# 05_UART.net
KiCad netlist of a schematic drawn in Altium Designer
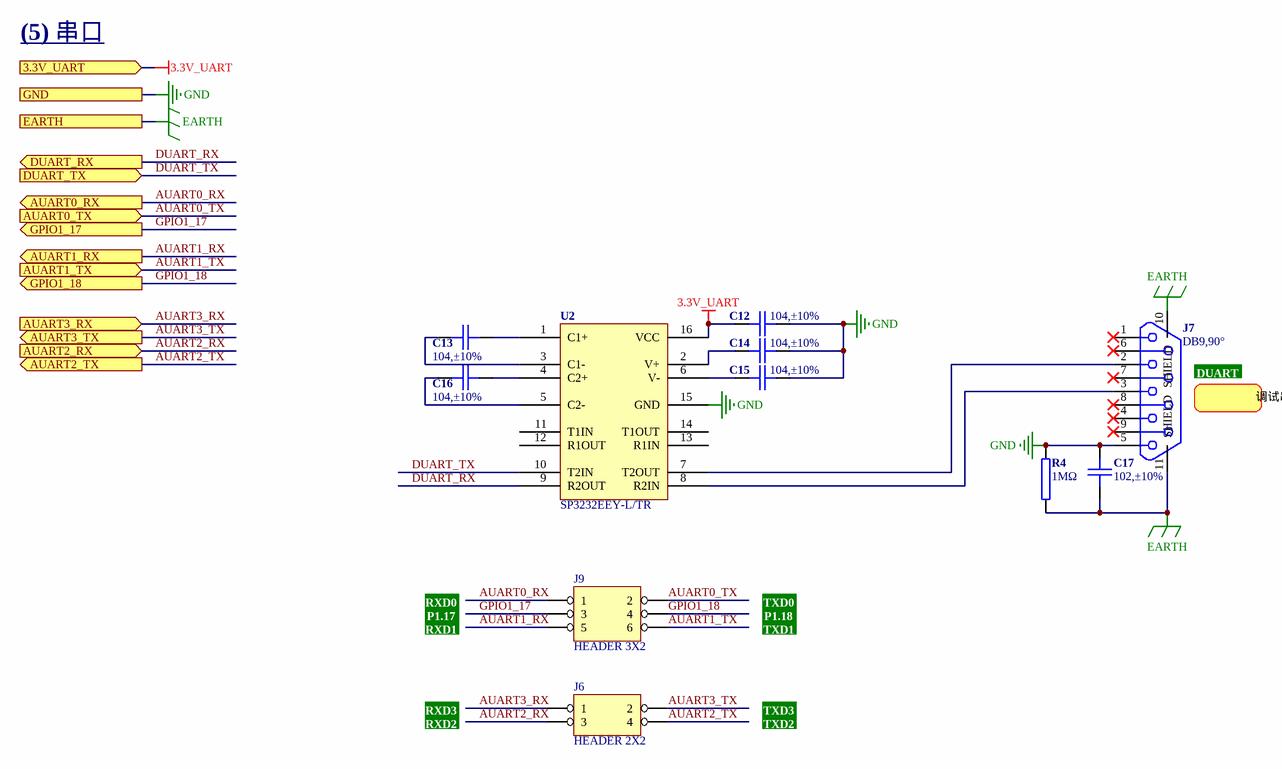
[diagram p0: 05. UART.SchDoc]

(export (version "E")
  (design (tool "Eeschema 10.0.6"))
  (components
    (comp (ref "C12")
      (value "104,±10%")
      (footprint "0603C")
      (description "104,±10%,50V,X7R,0603,*,RoHS")
      (libsource (lib "ErpMaterialData") (part "CAP1"))
    )
    (comp (ref "C13")
      (value "104,±10%")
      (footprint "0603C")
      (description "104,±10%,50V,X7R,0603,*,RoHS")
      (libsource (lib "ErpMaterialData") (part "CAP1"))
    )
    (comp (ref "C14")
      (value "104,±10%")
      (footprint "0603C")
      (description "104,±10%,50V,X7R,0603,*,RoHS")
      (libsource (lib "ErpMaterialData") (part "CAP1"))
    )
    (comp (ref "C15")
      (value "104,±10%")
      (footprint "0603C")
      (description "104,±10%,50V,X7R,0603,*,RoHS")
      (libsource (lib "ErpMaterialData") (part "CAP1"))
    )
    (comp (ref "C16")
      (value "104,±10%")
      (footprint "0603C")
      (description "104,±10%,50V,X7R,0603,*,RoHS")
      (libsource (lib "ErpMaterialData") (part "CAP1"))
    )
    (comp (ref "C17")
      (value "102,±10%")
      (footprint "1206C")
      (description "102,±10%,2KV,X7R,1206,*,RoHS")
      (libsource (lib "ErpMaterialData") (part "CAP1"))
    )
    (comp (ref "J6") (value "HEADER 2X2") (footprint "IDC-4") (libsource (lib "无需物料号元件") (part "HEADER 2X2")))
    (comp (ref "J7")
      (value "DB9,90°")
      (footprint "DB-9RA/F")
      (description "DB9,90°,孔,铆合,带螺丝")
      (fields (field (name "Comment") "DB9"))
      (libsource (lib "ErpMaterialData") (part "DB9"))
    )
    (comp (ref "J9") (value "HEADER 3X2") (footprint "IDC-6") (libsource (lib "无需物料号元件") (part "HEADER 3X2")))
    (comp (ref "R4")
      (value "1MΩ")
      (footprint "1206R")
      (description "1MΩ,1206,RoHS")
      (libsource (lib "ErpMaterialData") (part "RES2"))
    )
    (comp (ref "U2")
      (value "SP3232EEY-L/TR")
      (footprint "SOP65P640X120-16N")
      (description "SP3232EEY-L/TR,TSSOP-16,EXAR,RoHS")
      (fields (field (name "Comment") "SP3232E"))
      (libsource (lib "ErpMaterialData") (part "SP3232E"))
    )
  )
  (nets
    (net (code "1") (name "/AUART0_RX") (class "Default")
      (node (ref "J9") (pin "1") (pinfunction "1_1") (pintype "passive"))
    )
    (net (code "2") (name "/AUART0_TX") (class "Default")
      (node (ref "J9") (pin "2") (pinfunction "2_2") (pintype "passive"))
    )
    (net (code "3") (name "/AUART1_RX") (class "Default")
      (node (ref "J9") (pin "5") (pinfunction "5_5") (pintype "passive"))
    )
    (net (code "4") (name "/AUART1_TX") (class "Default")
      (node (ref "J9") (pin "6") (pinfunction "6_6") (pintype "passive"))
    )
    (net (code "5") (name "/AUART2_RX") (class "Default")
      (node (ref "J6") (pin "3") (pinfunction "3_3") (pintype "passive"))
    )
    (net (code "6") (name "/AUART2_TX") (class "Default")
      (node (ref "J6") (pin "4") (pinfunction "4_4") (pintype "passive"))
    )
    (net (code "7") (name "/AUART3_RX") (class "Default")
      (node (ref "J6") (pin "1") (pinfunction "1_1") (pintype "passive"))
    )
    (net (code "8") (name "/AUART3_TX") (class "Default")
      (node (ref "J6") (pin "2") (pinfunction "2_2") (pintype "passive"))
    )
    (net (code "9") (name "/DUART_RX") (class "Default")
      (node (ref "U2") (pin "9") (pinfunction "R2OUT_9") (pintype "passive"))
    )
    (net (code "10") (name "/DUART_TX") (class "Default")
      (node (ref "U2") (pin "10") (pinfunction "T2IN_10") (pintype "passive"))
    )
    (net (code "11") (name "/GPIO1_17") (class "Default")
      (node (ref "J9") (pin "3") (pinfunction "3_3") (pintype "passive"))
    )
    (net (code "12") (name "/GPIO1_18") (class "Default")
      (node (ref "J9") (pin "4") (pinfunction "4_4") (pintype "passive"))
    )
    (net (code "13") (name "3.3V_UART") (class "Default")
      (node (ref "C12") (pin "1") (pinfunction "1_1") (pintype "passive"))
      (node (ref "U2") (pin "16") (pinfunction "VCC_16") (pintype "passive"))
    )
    (net (code "14") (name "EARTH") (class "Default")
      (node (ref "C17") (pin "2") (pinfunction "2_2") (pintype "passive"))
      (node (ref "J7") (pin "10") (pinfunction "SHIELD_10") (pintype "passive"))
      (node (ref "J7") (pin "11") (pinfunction "SHIELD_11") (pintype "passive"))
      (node (ref "R4") (pin "1") (pinfunction "1_1") (pintype "passive"))
    )
    (net (code "15") (name "GND") (class "Default")
      (node (ref "C12") (pin "2") (pinfunction "2_2") (pintype "passive"))
      (node (ref "C14") (pin "2") (pinfunction "2_2") (pintype "passive"))
      (node (ref "C15") (pin "2") (pinfunction "2_2") (pintype "passive"))
      (node (ref "C17") (pin "1") (pinfunction "1_1") (pintype "passive"))
      (node (ref "J7") (pin "5") (pinfunction "5_5") (pintype "passive"))
      (node (ref "R4") (pin "2") (pinfunction "2_2") (pintype "passive"))
      (node (ref "U2") (pin "15") (pinfunction "GND_15") (pintype "passive"))
    )
    (net (code "16") (name "Net-(U2-C1+)") (class "Default")
      (node (ref "C13") (pin "2") (pinfunction "2_2") (pintype "passive"))
      (node (ref "U2") (pin "1") (pinfunction "C1+_1") (pintype "passive"))
    )
    (net (code "17") (name "Net-(U2-C1-)") (class "Default")
      (node (ref "C13") (pin "1") (pinfunction "1_1") (pintype "passive"))
      (node (ref "U2") (pin "3") (pinfunction "C1-_3") (pintype "passive"))
    )
    (net (code "18") (name "Net-(U2-C2+)") (class "Default")
      (node (ref "C16") (pin "2") (pinfunction "2_2") (pintype "passive"))
      (node (ref "U2") (pin "4") (pinfunction "C2+_4") (pintype "passive"))
    )
    (net (code "19") (name "Net-(U2-C2-)") (class "Default")
      (node (ref "C16") (pin "1") (pinfunction "1_1") (pintype "passive"))
      (node (ref "U2") (pin "5") (pinfunction "C2-_5") (pintype "passive"))
    )
    (net (code "20") (name "Net-(U2-R2IN)") (class "Default")
      (node (ref "J7") (pin "3") (pinfunction "3_3") (pintype "passive"))
      (node (ref "U2") (pin "8") (pinfunction "R2IN_8") (pintype "passive"))
    )
    (net (code "21") (name "Net-(U2-T2OUT)") (class "Default")
      (node (ref "J7") (pin "2") (pinfunction "2_2") (pintype "passive"))
      (node (ref "U2") (pin "7") (pinfunction "T2OUT_7") (pintype "passive"))
    )
    (net (code "22") (name "Net-(U2-V+)") (class "Default")
      (node (ref "C14") (pin "1") (pinfunction "1_1") (pintype "passive"))
      (node (ref "U2") (pin "2") (pinfunction "V+_2") (pintype "passive"))
    )
    (net (code "23") (name "Net-(U2-V-)") (class "Default")
      (node (ref "C15") (pin "1") (pinfunction "1_1") (pintype "passive"))
      (node (ref "U2") (pin "6") (pinfunction "V-_6") (pintype "passive"))
    )
    (net (code "24") (name "unconnected-(J7-Pad1)") (class "Default")
      (node (ref "J7") (pin "1") (pinfunction "1_1") (pintype "passive+no_connect"))
    )
    (net (code "25") (name "unconnected-(J7-Pad4)") (class "Default")
      (node (ref "J7") (pin "4") (pinfunction "4_4") (pintype "passive+no_connect"))
    )
    (net (code "26") (name "unconnected-(J7-Pad6)") (class "Default")
      (node (ref "J7") (pin "6") (pinfunction "6_6") (pintype "passive+no_connect"))
    )
    (net (code "27") (name "unconnected-(J7-Pad7)") (class "Default")
      (node (ref "J7") (pin "7") (pinfunction "7_7") (pintype "passive+no_connect"))
    )
    (net (code "28") (name "unconnected-(J7-Pad8)") (class "Default")
      (node (ref "J7") (pin "8") (pinfunction "8_8") (pintype "passive+no_connect"))
    )
    (net (code "29") (name "unconnected-(J7-Pad9)") (class "Default")
      (node (ref "J7") (pin "9") (pinfunction "9_9") (pintype "passive+no_connect"))
    )
    (net (code "30") (name "unconnected-(U2-R1IN-Pad13)") (class "Default")
      (node (ref "U2") (pin "13") (pinfunction "R1IN_13") (pintype "passive"))
    )
    (net (code "31") (name "unconnected-(U2-R1OUT-Pad12)") (class "Default")
      (node (ref "U2") (pin "12") (pinfunction "R1OUT_12") (pintype "passive"))
    )
    (net (code "32") (name "unconnected-(U2-T1IN-Pad11)") (class "Default")
      (node (ref "U2") (pin "11") (pinfunction "T1IN_11") (pintype "passive"))
    )
    (net (code "33") (name "unconnected-(U2-T1OUT-Pad14)") (class "Default")
      (node (ref "U2") (pin "14") (pinfunction "T1OUT_14") (pintype "passive"))
    )
  )
)
